# Charge_Interface.net
KiCad netlist of a schematic drawn in Altium Designer
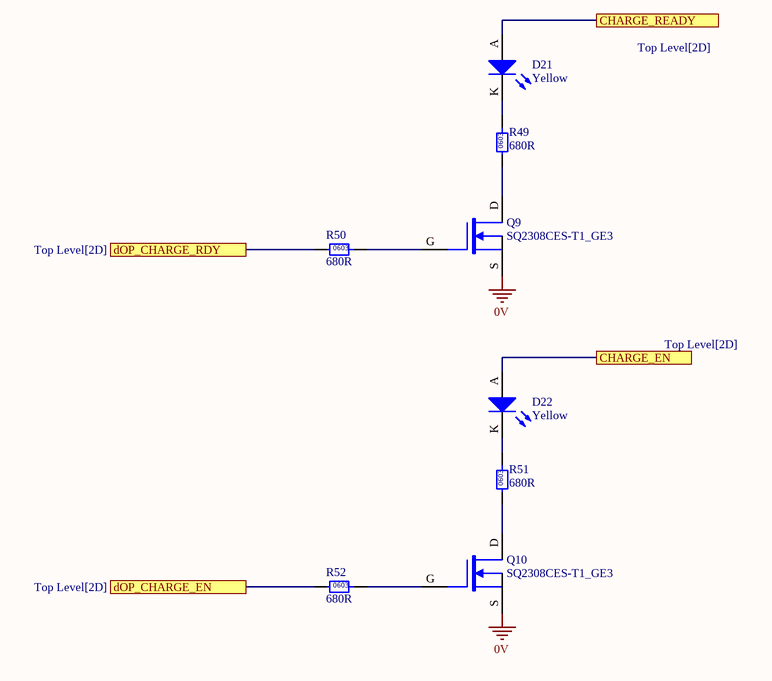
[diagram p0: Charge Interface.SchDoc]

(export (version "E")
  (design (tool "Eeschema 10.0.6"))
  (components
    (comp (ref "D21")
      (value "Yellow")
      (footprint "0805 LED")
      (description "Yellow LED Indication - Discrete 1.75V 0805 (2012 Metric)")
      (fields (field (name "PART NUMBER") "SML-211YTT86") (field (name "MANUFACTURER") "ROHM Semiconductor"))
      (libsource (lib "ts_standard_library") (part "LED"))
    )
    (comp (ref "D22")
      (value "Yellow")
      (footprint "0805 LED")
      (description "Yellow LED Indication - Discrete 1.75V 0805 (2012 Metric)")
      (fields (field (name "PART NUMBER") "SML-211YTT86") (field (name "MANUFACTURER") "ROHM Semiconductor"))
      (libsource (lib "ts_standard_library") (part "LED"))
    )
    (comp (ref "Q9")
      (value "SQ2308CES-T1_GE3")
      (footprint "VSHY SOT-23-3")
      (description "MOSFET N-CH 60V 2.3A SOT23")
      (fields
        (field (name "MANUFACTURER") "Vishay Siliconix")
        (field (name "DIGIKEY PART NUMBER") "SQ2308CES-T1_GE3CT-ND")
        (field (name "PUBLISHER") "Altium Limited")
      )
      (libsource (lib "ts_standard_library") (part "MOSFET-N"))
    )
    (comp (ref "Q10")
      (value "SQ2308CES-T1_GE3")
      (footprint "VSHY SOT-23-3")
      (description "MOSFET N-CH 60V 2.3A SOT23")
      (fields
        (field (name "MANUFACTURER") "Vishay Siliconix")
        (field (name "DIGIKEY PART NUMBER") "SQ2308CES-T1_GE3CT-ND")
        (field (name "PUBLISHER") "Altium Limited")
      )
      (libsource (lib "ts_standard_library") (part "MOSFET-N"))
    )
    (comp (ref "R49")
      (value "680R")
      (footprint "0603")
      (fields
        (field (name "PART NUMBER") "RC0603JR-13680RL")
        (field (name "MANUFACTURER") "YAGEO")
        (field (name "TOLERANCE") "0.01")
      )
      (libsource (lib "ts_standard_library") (part "Resistor 0603"))
    )
    (comp (ref "R50")
      (value "680R")
      (footprint "0603")
      (fields
        (field (name "PART NUMBER") "RC0603JR-13680RL")
        (field (name "MANUFACTURER") "YAGEO")
        (field (name "TOLERANCE") "0.01")
      )
      (libsource (lib "ts_standard_library") (part "Resistor 0603"))
    )
    (comp (ref "R51")
      (value "680R")
      (footprint "0603")
      (fields
        (field (name "PART NUMBER") "RC0603JR-13680RL")
        (field (name "MANUFACTURER") "YAGEO")
        (field (name "TOLERANCE") "0.01")
      )
      (libsource (lib "ts_standard_library") (part "Resistor 0603"))
    )
    (comp (ref "R52")
      (value "680R")
      (footprint "0603")
      (fields
        (field (name "PART NUMBER") "RC0603JR-13680RL")
        (field (name "MANUFACTURER") "YAGEO")
        (field (name "TOLERANCE") "0.01")
      )
      (libsource (lib "ts_standard_library") (part "Resistor 0603"))
    )
  )
  (nets
    (net (code "1") (name "/CHARGE_EN") (class "Default")
      (node (ref "D22") (pin "A") (pinfunction "A_A") (pintype "passive"))
    )
    (net (code "2") (name "/CHARGE_READY") (class "Default")
      (node (ref "D21") (pin "A") (pinfunction "A_A") (pintype "passive"))
    )
    (net (code "3") (name "/dOP_CHARGE_EN") (class "Default")
      (node (ref "R52") (pin "1") (pinfunction "1_1") (pintype "passive"))
    )
    (net (code "4") (name "/dOP_CHARGE_RDY") (class "Default")
      (node (ref "R50") (pin "1") (pinfunction "1_1") (pintype "passive"))
    )
    (net (code "5") (name "0V") (class "Default")
      (node (ref "Q10") (pin "S") (pinfunction "S_S") (pintype "passive"))
      (node (ref "Q9") (pin "S") (pinfunction "S_S") (pintype "passive"))
    )
    (net (code "6") (name "Net-(D21-PadK)") (class "Default")
      (node (ref "D21") (pin "K") (pinfunction "K_K") (pintype "passive"))
      (node (ref "R49") (pin "2") (pinfunction "2_2") (pintype "passive"))
    )
    (net (code "7") (name "Net-(D22-PadK)") (class "Default")
      (node (ref "D22") (pin "K") (pinfunction "K_K") (pintype "passive"))
      (node (ref "R51") (pin "2") (pinfunction "2_2") (pintype "passive"))
    )
    (net (code "8") (name "Net-(Q9-PadD)") (class "Default")
      (node (ref "Q9") (pin "D") (pinfunction "D_D") (pintype "passive"))
      (node (ref "R49") (pin "1") (pinfunction "1_1") (pintype "passive"))
    )
    (net (code "9") (name "Net-(Q9-PadG)") (class "Default")
      (node (ref "Q9") (pin "G") (pinfunction "G_G") (pintype "passive"))
      (node (ref "R50") (pin "2") (pinfunction "2_2") (pintype "passive"))
    )
    (net (code "10") (name "Net-(Q10-PadD)") (class "Default")
      (node (ref "Q10") (pin "D") (pinfunction "D_D") (pintype "passive"))
      (node (ref "R51") (pin "1") (pinfunction "1_1") (pintype "passive"))
    )
    (net (code "11") (name "Net-(Q10-PadG)") (class "Default")
      (node (ref "Q10") (pin "G") (pinfunction "G_G") (pintype "passive"))
      (node (ref "R52") (pin "2") (pinfunction "2_2") (pintype "passive"))
    )
  )
)
